# USB-FTDI-ESP.net
KiCad netlist of a schematic drawn in EAGLE
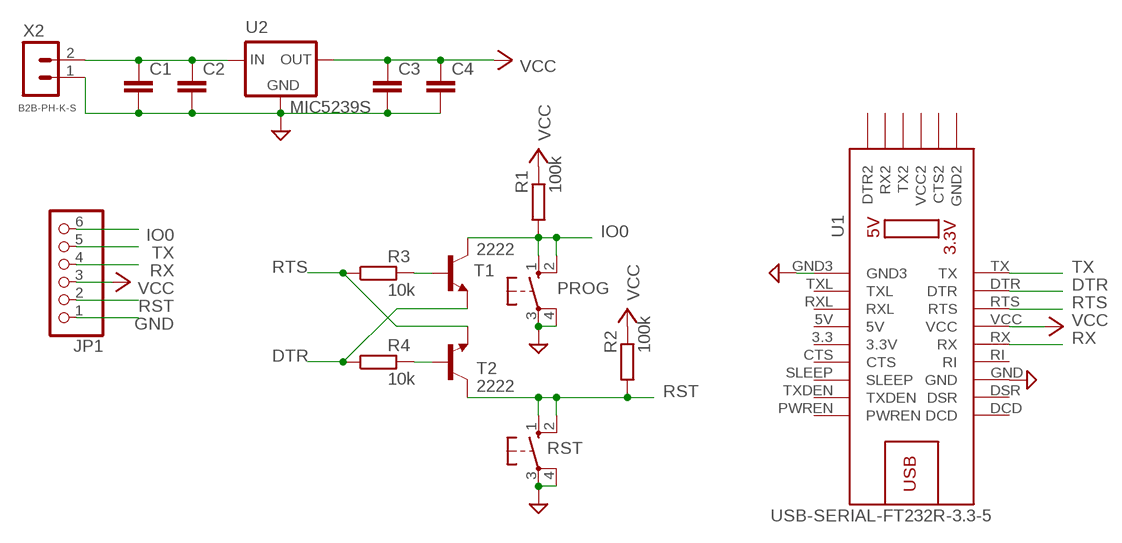
[diagram p0: schematic, sheet 1]

(export (version "E")
  (design (tool "Eeschema 10.0.6"))
  (components
    (comp (ref "C1")
      (value "C-EUC1206K")
      (footprint "eagle-import:C1206K")
      (libsource (lib "eagle-import") (part "C-EUC1206K"))
    )
    (comp (ref "C2")
      (value "C-EUC1206K")
      (footprint "eagle-import:C1206K")
      (libsource (lib "eagle-import") (part "C-EUC1206K"))
    )
    (comp (ref "C3")
      (value "C-EUC1206K")
      (footprint "eagle-import:C1206K")
      (libsource (lib "eagle-import") (part "C-EUC1206K"))
    )
    (comp (ref "C4")
      (value "C-EUC1206K")
      (footprint "eagle-import:C1206K")
      (libsource (lib "eagle-import") (part "C-EUC1206K"))
    )
    (comp (ref "JP1")
      (value "PINHD-1X6")
      (footprint "eagle-import:1X06")
      (libsource (lib "eagle-import") (part "PINHD-1X6"))
    )
    (comp (ref "PROG")
      (value "10-XX")
      (footprint "eagle-import:B3F-10XX")
      (fields (field (name "MPN") "B3F-1000"))
      (libsource (lib "eagle-import") (part "10-XX"))
    )
    (comp (ref "R1")
      (value "100k")
      (footprint "eagle-import:R1206")
      (libsource (lib "eagle-import") (part "RR1206"))
    )
    (comp (ref "R2")
      (value "100k")
      (footprint "eagle-import:R1206")
      (libsource (lib "eagle-import") (part "RR1206"))
    )
    (comp (ref "R3")
      (value "10k")
      (footprint "eagle-import:R1206")
      (libsource (lib "eagle-import") (part "RR1206"))
    )
    (comp (ref "R4")
      (value "10k")
      (footprint "eagle-import:R1206")
      (libsource (lib "eagle-import") (part "RR1206"))
    )
    (comp (ref "RST")
      (value "10-XX")
      (footprint "eagle-import:B3F-10XX")
      (fields (field (name "MPN") "B3F-1000"))
      (libsource (lib "eagle-import") (part "10-XX"))
    )
    (comp (ref "T1")
      (value "2222")
      (footprint "eagle-import:SOT23-BEC")
      (libsource (lib "eagle-import") (part "-NPN-SOT23-BECMMBT2222ALT1"))
    )
    (comp (ref "T2")
      (value "2222")
      (footprint "eagle-import:SOT23-BEC")
      (libsource (lib "eagle-import") (part "-NPN-SOT23-BECMMBT2222ALT1"))
    )
    (comp (ref "U1")
      (value "USB-SERIAL-FT232R-3.3-5")
      (footprint "eagle-import:USB-SERIAL-FT232R-3.3-5")
      (libsource (lib "eagle-import") (part "USB-SERIAL-FT232R-3.3-5"))
    )
    (comp (ref "U2")
      (value "MIC5239S")
      (footprint "eagle-import:SOT223")
      (libsource (lib "eagle-import") (part "MIC5239S"))
    )
    (comp (ref "X2")
      (value "B2B-PH-K-S")
      (footprint "eagle-import:B2B-PH-K-S")
      (libsource (lib "eagle-import") (part "B2B-PH-K-S"))
    )
  )
  (nets
    (net (code "1") (name "/DTR") (class "Default")
      (node (ref "R4") (pin "1") (pinfunction "1_1") (pintype "passive"))
      (node (ref "T1") (pin "E") (pinfunction "E_E") (pintype "passive"))
      (node (ref "U1") (pin "DTR") (pinfunction "DTR_DTR") (pintype "bidirectional"))
    )
    (net (code "2") (name "/IO0") (class "Default")
      (node (ref "JP1") (pin "6") (pinfunction "6_6") (pintype "passive"))
      (node (ref "PROG") (pin "1") (pinfunction "S_1") (pintype "passive"))
      (node (ref "PROG") (pin "2") (pinfunction "S1_2") (pintype "passive"))
      (node (ref "R1") (pin "1") (pinfunction "1_1") (pintype "passive"))
      (node (ref "T1") (pin "C") (pinfunction "C_C") (pintype "passive"))
    )
    (net (code "3") (name "/RST") (class "Default")
      (node (ref "JP1") (pin "2") (pinfunction "2_2") (pintype "passive"))
      (node (ref "R2") (pin "1") (pinfunction "1_1") (pintype "passive"))
      (node (ref "RST") (pin "1") (pinfunction "S_1") (pintype "passive"))
      (node (ref "RST") (pin "2") (pinfunction "S1_2") (pintype "passive"))
      (node (ref "T2") (pin "C") (pinfunction "C_C") (pintype "passive"))
    )
    (net (code "4") (name "/RTS") (class "Default")
      (node (ref "R3") (pin "1") (pinfunction "1_1") (pintype "passive"))
      (node (ref "T2") (pin "E") (pinfunction "E_E") (pintype "passive"))
      (node (ref "U1") (pin "RTS") (pinfunction "RTS_RTS") (pintype "bidirectional"))
    )
    (net (code "5") (name "/RX") (class "Default")
      (node (ref "JP1") (pin "4") (pinfunction "4_4") (pintype "passive"))
      (node (ref "U1") (pin "RX") (pinfunction "RX_RX") (pintype "bidirectional"))
    )
    (net (code "6") (name "/TX") (class "Default")
      (node (ref "JP1") (pin "5") (pinfunction "5_5") (pintype "passive"))
      (node (ref "U1") (pin "TX") (pinfunction "TX_TX") (pintype "bidirectional"))
    )
    (net (code "7") (name "/VCC2") (class "Default")
      (node (ref "U1") (pin "VCC2") (pinfunction "VCC2_VCC2") (pintype "power_in"))
    )
    (net (code "8") (name "GND") (class "Default")
      (node (ref "C1") (pin "2") (pinfunction "2_2") (pintype "passive"))
      (node (ref "C2") (pin "2") (pinfunction "2_2") (pintype "passive"))
      (node (ref "C3") (pin "2") (pinfunction "2_2") (pintype "passive"))
      (node (ref "C4") (pin "2") (pinfunction "2_2") (pintype "passive"))
      (node (ref "JP1") (pin "1") (pinfunction "1_1") (pintype "passive"))
      (node (ref "PROG") (pin "3") (pinfunction "P_3") (pintype "passive"))
      (node (ref "PROG") (pin "4") (pinfunction "P1_4") (pintype "passive"))
      (node (ref "RST") (pin "3") (pinfunction "P_3") (pintype "passive"))
      (node (ref "RST") (pin "4") (pinfunction "P1_4") (pintype "passive"))
      (node (ref "U1") (pin "GND") (pinfunction "GND_GND") (pintype "bidirectional"))
      (node (ref "U1") (pin "GND3") (pinfunction "GND3_GND3") (pintype "bidirectional"))
      (node (ref "U2") (pin "2") (pinfunction "GND_2") (pintype "passive"))
      (node (ref "U2") (pin "4") (pinfunction "GND_4") (pintype "passive"))
      (node (ref "X2") (pin "1") (pinfunction "1_1") (pintype "passive"))
    )
    (net (code "9") (name "Net-(R3-Pad2)") (class "Default")
      (node (ref "R3") (pin "2") (pinfunction "2_2") (pintype "passive"))
      (node (ref "T1") (pin "B") (pinfunction "B_B") (pintype "passive"))
    )
    (net (code "10") (name "Net-(R4-Pad2)") (class "Default")
      (node (ref "R4") (pin "2") (pinfunction "2_2") (pintype "passive"))
      (node (ref "T2") (pin "B") (pinfunction "B_B") (pintype "passive"))
    )
    (net (code "11") (name "Net-(U2-IN)") (class "Default")
      (node (ref "C1") (pin "1") (pinfunction "1_1") (pintype "passive"))
      (node (ref "C2") (pin "1") (pinfunction "1_1") (pintype "passive"))
      (node (ref "U2") (pin "1") (pinfunction "IN_1") (pintype "input"))
      (node (ref "X2") (pin "2") (pinfunction "2_2") (pintype "passive"))
    )
    (net (code "12") (name "VCC") (class "Default")
      (node (ref "C3") (pin "1") (pinfunction "1_1") (pintype "passive"))
      (node (ref "C4") (pin "1") (pinfunction "1_1") (pintype "passive"))
      (node (ref "JP1") (pin "3") (pinfunction "3_3") (pintype "passive"))
      (node (ref "R1") (pin "2") (pinfunction "2_2") (pintype "passive"))
      (node (ref "R2") (pin "2") (pinfunction "2_2") (pintype "passive"))
      (node (ref "U1") (pin "VCC") (pinfunction "VCC_VCC") (pintype "bidirectional"))
      (node (ref "U2") (pin "3") (pinfunction "OUT_3") (pintype "passive"))
    )
    (net (code "13") (name "unconnected-(U1-3.3V-Pad3.3)") (class "Default")
      (node (ref "U1") (pin "3.3") (pinfunction "3.3V_3.3") (pintype "bidirectional"))
    )
    (net (code "14") (name "unconnected-(U1-Pad5V)") (class "Default")
      (node (ref "U1") (pin "5V") (pinfunction "5V_5V") (pintype "bidirectional"))
    )
    (net (code "15") (name "unconnected-(U1-PadCTS)") (class "Default")
      (node (ref "U1") (pin "CTS") (pinfunction "CTS_CTS") (pintype "bidirectional"))
    )
    (net (code "16") (name "unconnected-(U1-PadCTS2)") (class "Default")
      (node (ref "U1") (pin "CTS2") (pinfunction "CTS2_CTS2") (pintype "bidirectional"))
    )
    (net (code "17") (name "unconnected-(U1-PadDCD)") (class "Default")
      (node (ref "U1") (pin "DCD") (pinfunction "DCD_DCD") (pintype "bidirectional"))
    )
    (net (code "18") (name "unconnected-(U1-PadDSR)") (class "Default")
      (node (ref "U1") (pin "DSR") (pinfunction "DSR_DSR") (pintype "bidirectional"))
    )
    (net (code "19") (name "unconnected-(U1-PadDTR2)") (class "Default")
      (node (ref "U1") (pin "DTR2") (pinfunction "DTR2_DTR2") (pintype "bidirectional"))
    )
    (net (code "20") (name "unconnected-(U1-PadGND2)") (class "Default")
      (node (ref "U1") (pin "GND2") (pinfunction "GND2_GND2") (pintype "bidirectional"))
    )
    (net (code "21") (name "unconnected-(U1-PadPWREN)") (class "Default")
      (node (ref "U1") (pin "PWREN") (pinfunction "PWREN_PWREN") (pintype "bidirectional"))
    )
    (net (code "22") (name "unconnected-(U1-PadRI)") (class "Default")
      (node (ref "U1") (pin "RI") (pinfunction "RI_RI") (pintype "bidirectional"))
    )
    (net (code "23") (name "unconnected-(U1-PadRX2)") (class "Default")
      (node (ref "U1") (pin "RX2") (pinfunction "RX2_RX2") (pintype "bidirectional"))
    )
    (net (code "24") (name "unconnected-(U1-PadRXL)") (class "Default")
      (node (ref "U1") (pin "RXL") (pinfunction "RXL_RXL") (pintype "bidirectional"))
    )
    (net (code "25") (name "unconnected-(U1-PadSLEEP)") (class "Default")
      (node (ref "U1") (pin "SLEEP") (pinfunction "SLEEP_SLEEP") (pintype "bidirectional"))
    )
    (net (code "26") (name "unconnected-(U1-PadTX2)") (class "Default")
      (node (ref "U1") (pin "TX2") (pinfunction "TX2_TX2") (pintype "bidirectional"))
    )
    (net (code "27") (name "unconnected-(U1-PadTXDEN)") (class "Default")
      (node (ref "U1") (pin "TXDEN") (pinfunction "TXDEN_TXDEN") (pintype "bidirectional"))
    )
    (net (code "28") (name "unconnected-(U1-PadTXL)") (class "Default")
      (node (ref "U1") (pin "TXL") (pinfunction "TXL_TXL") (pintype "bidirectional"))
    )
  )
)
